# samd21g_minimal_board.net
KiCad netlist of a schematic drawn in EAGLE
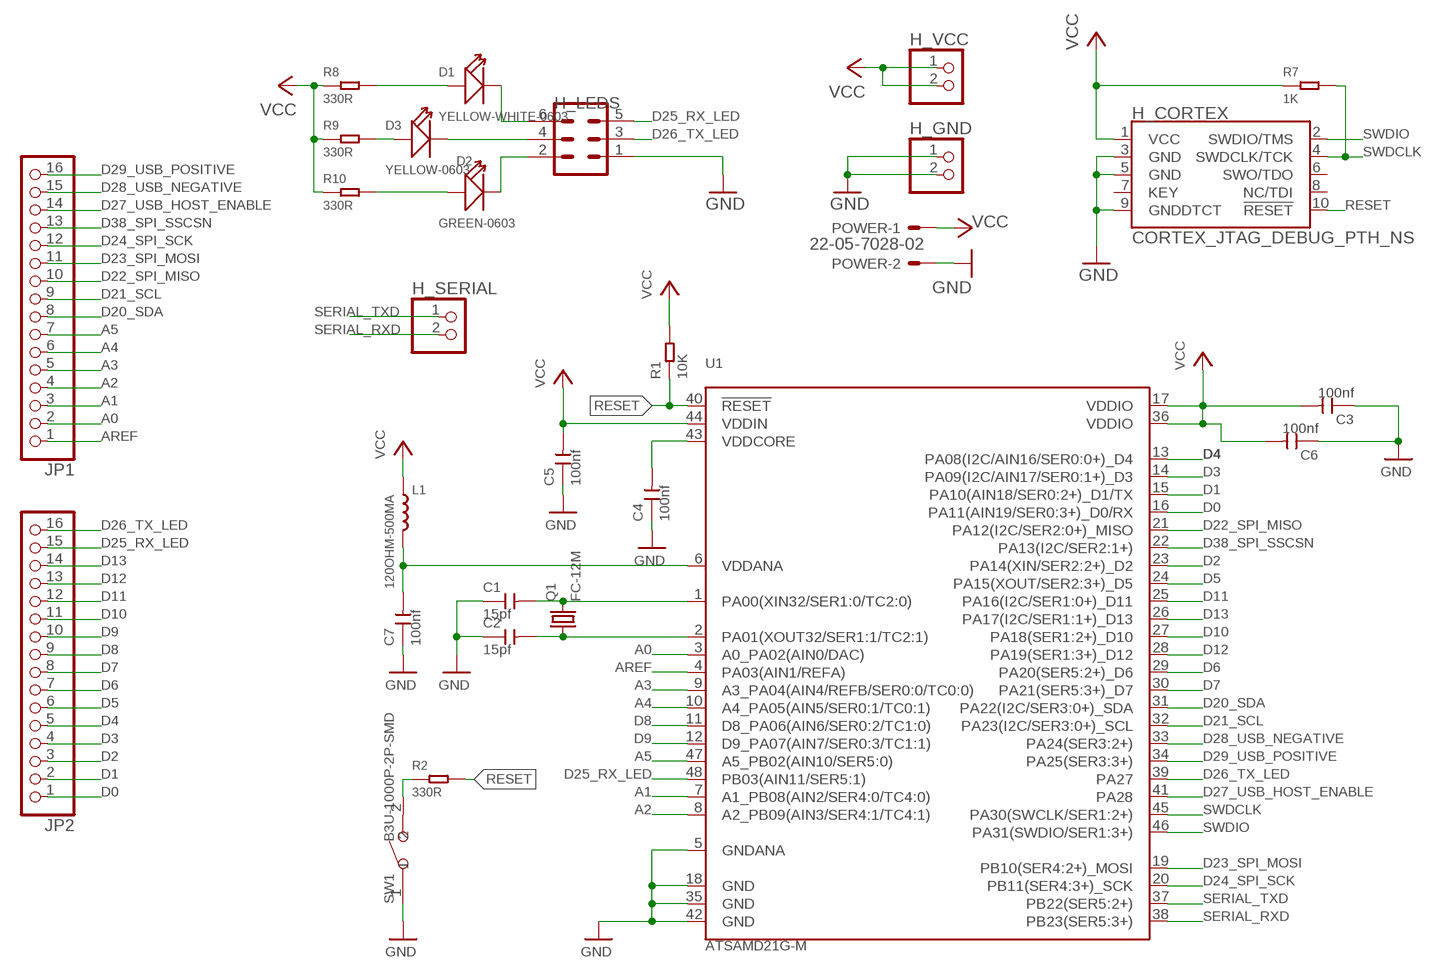
[diagram p0: schematic, sheet 1]

(export (version "E")
  (design (tool "Eeschema 10.0.6"))
  (components
    (comp (ref "C1")
      (value "15pf")
      (footprint "eagle-import:C0402")
      (fields (field (name "MPN") "GRM1555C1H150JA01D"))
      (libsource (lib "eagle-import") (part "CERAMIC-15PF-50V-5%-NPO(0402)"))
    )
    (comp (ref "C2")
      (value "15pf")
      (footprint "eagle-import:C0402")
      (fields (field (name "MPN") "GRM1555C1H150JA01D"))
      (libsource (lib "eagle-import") (part "CERAMIC-15PF-50V-5%-NPO(0402)"))
    )
    (comp (ref "C3")
      (value "100nf")
      (footprint "eagle-import:C0805")
      (fields (field (name "MPN") "CC0805KRX7R9BB104"))
      (libsource (lib "eagle-import") (part "CERAMIC-100NF-50V-10%-X7R(0805)"))
    )
    (comp (ref "C4")
      (value "100nf")
      (footprint "eagle-import:C0805")
      (fields (field (name "MPN") "CC0805KRX7R9BB104"))
      (libsource (lib "eagle-import") (part "CERAMIC-100NF-50V-10%-X7R(0805)"))
    )
    (comp (ref "C5")
      (value "100nf")
      (footprint "eagle-import:C0805")
      (fields (field (name "MPN") "CC0805KRX7R9BB104"))
      (libsource (lib "eagle-import") (part "CERAMIC-100NF-50V-10%-X7R(0805)"))
    )
    (comp (ref "C6")
      (value "100nf")
      (footprint "eagle-import:C0805")
      (fields (field (name "MPN") "CC0805KRX7R9BB104"))
      (libsource (lib "eagle-import") (part "CERAMIC-100NF-50V-10%-X7R(0805)"))
    )
    (comp (ref "C7")
      (value "100nf")
      (footprint "eagle-import:C0805")
      (fields (field (name "MPN") "CC0805KRX7R9BB104"))
      (libsource (lib "eagle-import") (part "CERAMIC-100NF-50V-10%-X7R(0805)"))
    )
    (comp (ref "D1")
      (value "YELLOW-WHITE-0603")
      (footprint "eagle-import:LED-0603")
      (fields (field (name "MPN") "ADL-0603W"))
      (libsource (lib "eagle-import") (part "SMD-LED-YELLOW-WHITE(0603)"))
    )
    (comp (ref "D2")
      (value "GREEN-0603")
      (footprint "eagle-import:LED-0603")
      (fields (field (name "MPN") "19-217-G7C-AN1P2-3T"))
      (libsource (lib "eagle-import") (part "SMD-LED-CLEAR-GREEN(0603)"))
    )
    (comp (ref "D3")
      (value "YELLOW-0603")
      (footprint "eagle-import:LED-0603")
      (fields (field (name "MPN") "19-217-Y5C-AM1N1VY-3T"))
      (libsource (lib "eagle-import") (part "SMD-LED-CLEAR-YELLOW(0603)"))
    )
    (comp (ref "H_CORTEX")
      (value "CORTEX_JTAG_DEBUG_PTH_NS")
      (footprint "eagle-import:2X5-PTH-1.27MM-NO_SILK")
      (libsource (lib "eagle-import") (part "CORTEX_JTAG_DEBUG_PTH_NS"))
    )
    (comp (ref "H_GND")
      (value "PINHD-1X2")
      (footprint "eagle-import:1X02")
      (libsource (lib "eagle-import") (part "PINHD-1X2"))
    )
    (comp (ref "H_LEDS")
      (value "M_2R03_50MIL-V2")
      (footprint "eagle-import:M_2R03_50MIL-V2")
      (libsource (lib "eagle-import") (part "M_2R03_50MIL-V2"))
    )
    (comp (ref "H_SERIAL")
      (value "PINHD-1X2")
      (footprint "eagle-import:1X02")
      (libsource (lib "eagle-import") (part "PINHD-1X2"))
    )
    (comp (ref "H_VCC")
      (value "PINHD-1X2")
      (footprint "eagle-import:1X02")
      (libsource (lib "eagle-import") (part "PINHD-1X2"))
    )
    (comp (ref "JP1")
      (value "PINHD-1X16")
      (footprint "eagle-import:1X16")
      (libsource (lib "eagle-import") (part "PINHD-1X16"))
    )
    (comp (ref "JP2")
      (value "PINHD-1X16")
      (footprint "eagle-import:1X16")
      (libsource (lib "eagle-import") (part "PINHD-1X16"))
    )
    (comp (ref "L1")
      (value "120OHM-500MA")
      (footprint "eagle-import:L0603")
      (fields (field (name "MPN") "BLM18AG121SN1D"))
      (libsource (lib "eagle-import") (part "SMD-FERRITE-CHIP-120-OHM-500MA(0603)"))
    )
    (comp (ref "POWER")
      (value "22-05-7028-02")
      (footprint "eagle-import:7395-02")
      (fields (field (name "MF") "MOLEX"))
      (libsource (lib "eagle-import") (part "22-?-0205-7028"))
    )
    (comp (ref "Q1")
      (value "FC-12M")
      (footprint "eagle-import:FC-12M")
      (libsource (lib "eagle-import") (part "FC-12M"))
    )
    (comp (ref "R1")
      (value "10K")
      (footprint "eagle-import:R0805")
      (fields (field (name "MPN") "RC0805FR-0710KL"))
      (libsource (lib "eagle-import") (part "SMD-RES-10K-1%-1/8W(0805)"))
    )
    (comp (ref "R2")
      (value "330R")
      (footprint "eagle-import:R0805")
      (fields (field (name "MPN") "RC0805JR-071KL") (field (name "MPN_1") "RC0805FR-07330RL"))
      (libsource (lib "eagle-import") (part "SMD-RES-330R-1%-1/8W(0805)"))
    )
    (comp (ref "R7")
      (value "1K")
      (footprint "eagle-import:R0805")
      (fields (field (name "MPN") "RC0805JR-071KL"))
      (libsource (lib "eagle-import") (part "SMD-RES-1K-5%-1/8W(0805)"))
    )
    (comp (ref "R8")
      (value "330R")
      (footprint "eagle-import:R0805")
      (fields (field (name "MPN") "RC0805JR-071KL") (field (name "MPN_1") "RC0805FR-07330RL"))
      (libsource (lib "eagle-import") (part "SMD-RES-330R-1%-1/8W(0805)"))
    )
    (comp (ref "R9")
      (value "330R")
      (footprint "eagle-import:R0805")
      (fields (field (name "MPN") "RC0805JR-071KL") (field (name "MPN_1") "RC0805FR-07330RL"))
      (libsource (lib "eagle-import") (part "SMD-RES-330R-1%-1/8W(0805)"))
    )
    (comp (ref "R10")
      (value "330R")
      (footprint "eagle-import:R0805")
      (fields (field (name "MPN") "RC0805JR-071KL") (field (name "MPN_1") "RC0805FR-07330RL"))
      (libsource (lib "eagle-import") (part "SMD-RES-330R-1%-1/8W(0805)"))
    )
    (comp (ref "SW1")
      (value "B3U-1000P-2P-SMD")
      (footprint "eagle-import:SW2-2.6-3.0X2.5X1.2+0.4MM")
      (fields (field (name "SPICEPREFIX") "B"))
      (libsource (lib "eagle-import") (part "SMD-BUTTON(2P-3.0X2.5X1.2+0.4MM)-B3U-1000P-2P-SMD"))
    )
    (comp (ref "U1")
      (value "ATSAMD21G-M")
      (footprint "eagle-import:QFN-48")
      (libsource (lib "eagle-import") (part "ATSAMD21G-M"))
    )
  )
  (nets
    (net (code "1") (name "/A0") (class "Default")
      (node (ref "JP1") (pin "2") (pinfunction "2_2") (pintype "passive"))
      (node (ref "U1") (pin "3") (pinfunction "A0_PA02(AIN0/DAC)_3") (pintype "bidirectional"))
    )
    (net (code "2") (name "/A1") (class "Default")
      (node (ref "JP1") (pin "3") (pinfunction "3_3") (pintype "passive"))
      (node (ref "U1") (pin "7") (pinfunction "A1_PB08(AIN2/SER4:0/TC4:0)_7") (pintype "bidirectional"))
    )
    (net (code "3") (name "/A2") (class "Default")
      (node (ref "JP1") (pin "4") (pinfunction "4_4") (pintype "passive"))
      (node (ref "U1") (pin "8") (pinfunction "A2_PB09(AIN3/SER4:1/TC4:1)_8") (pintype "bidirectional"))
    )
    (net (code "4") (name "/A3") (class "Default")
      (node (ref "JP1") (pin "5") (pinfunction "5_5") (pintype "passive"))
      (node (ref "U1") (pin "9") (pinfunction "A3_PA04(AIN4/REFB/SER0:0/TC0:0)_9") (pintype "bidirectional"))
    )
    (net (code "5") (name "/A4") (class "Default")
      (node (ref "JP1") (pin "6") (pinfunction "6_6") (pintype "passive"))
      (node (ref "U1") (pin "10") (pinfunction "A4_PA05(AIN5/SER0:1/TC0:1)_10") (pintype "bidirectional"))
    )
    (net (code "6") (name "/A5") (class "Default")
      (node (ref "JP1") (pin "7") (pinfunction "7_7") (pintype "passive"))
      (node (ref "U1") (pin "47") (pinfunction "A5_PB02(AIN10/SER5:0)_47") (pintype "bidirectional"))
    )
    (net (code "7") (name "/AREF") (class "Default")
      (node (ref "JP1") (pin "1") (pinfunction "1_1") (pintype "passive"))
      (node (ref "U1") (pin "4") (pinfunction "PA03(AIN1/REFA)_4") (pintype "bidirectional"))
    )
    (net (code "8") (name "/D0") (class "Default")
      (node (ref "JP2") (pin "1") (pinfunction "1_1") (pintype "passive"))
      (node (ref "U1") (pin "16") (pinfunction "PA11(AIN19/SER0:3+)_D0/RX_16") (pintype "bidirectional"))
    )
    (net (code "9") (name "/D1") (class "Default")
      (node (ref "JP2") (pin "2") (pinfunction "2_2") (pintype "passive"))
      (node (ref "U1") (pin "15") (pinfunction "PA10(AIN18/SER0:2+)_D1/TX_15") (pintype "bidirectional"))
    )
    (net (code "10") (name "/D2") (class "Default")
      (node (ref "JP2") (pin "3") (pinfunction "3_3") (pintype "passive"))
      (node (ref "U1") (pin "23") (pinfunction "PA14(XIN/SER2:2+)_D2_23") (pintype "bidirectional"))
    )
    (net (code "11") (name "/D3") (class "Default")
      (node (ref "JP2") (pin "4") (pinfunction "4_4") (pintype "passive"))
      (node (ref "U1") (pin "14") (pinfunction "PA09(I2C/AIN17/SER0:1+)_D3_14") (pintype "bidirectional"))
    )
    (net (code "12") (name "/D4") (class "Default")
      (node (ref "JP2") (pin "5") (pinfunction "5_5") (pintype "passive"))
      (node (ref "U1") (pin "13") (pinfunction "PA08(I2C/AIN16/SER0:0+)_D4_13") (pintype "bidirectional"))
    )
    (net (code "13") (name "/D5") (class "Default")
      (node (ref "JP2") (pin "6") (pinfunction "6_6") (pintype "passive"))
      (node (ref "U1") (pin "24") (pinfunction "PA15(XOUT/SER2:3+)_D5_24") (pintype "bidirectional"))
    )
    (net (code "14") (name "/D6") (class "Default")
      (node (ref "JP2") (pin "7") (pinfunction "7_7") (pintype "passive"))
      (node (ref "U1") (pin "29") (pinfunction "PA20(SER5:2+)_D6_29") (pintype "bidirectional"))
    )
    (net (code "15") (name "/D7") (class "Default")
      (node (ref "JP2") (pin "8") (pinfunction "8_8") (pintype "passive"))
      (node (ref "U1") (pin "30") (pinfunction "PA21(SER5:3+)_D7_30") (pintype "bidirectional"))
    )
    (net (code "16") (name "/D8") (class "Default")
      (node (ref "JP2") (pin "9") (pinfunction "9_9") (pintype "passive"))
      (node (ref "U1") (pin "11") (pinfunction "D8_PA06(AIN6/SER0:2/TC1:0)_11") (pintype "bidirectional"))
    )
    (net (code "17") (name "/D9") (class "Default")
      (node (ref "JP2") (pin "10") (pinfunction "10_10") (pintype "passive"))
      (node (ref "U1") (pin "12") (pinfunction "D9_PA07(AIN7/SER0:3/TC1:1)_12") (pintype "bidirectional"))
    )
    (net (code "18") (name "/D10") (class "Default")
      (node (ref "JP2") (pin "11") (pinfunction "11_11") (pintype "passive"))
      (node (ref "U1") (pin "27") (pinfunction "PA18(SER1:2+)_D10_27") (pintype "bidirectional"))
    )
    (net (code "19") (name "/D11") (class "Default")
      (node (ref "JP2") (pin "12") (pinfunction "12_12") (pintype "passive"))
      (node (ref "U1") (pin "25") (pinfunction "PA16(I2C/SER1:0+)_D11_25") (pintype "bidirectional"))
    )
    (net (code "20") (name "/D12") (class "Default")
      (node (ref "JP2") (pin "13") (pinfunction "13_13") (pintype "passive"))
      (node (ref "U1") (pin "28") (pinfunction "PA19(SER1:3+)_D12_28") (pintype "bidirectional"))
    )
    (net (code "21") (name "/D13") (class "Default")
      (node (ref "JP2") (pin "14") (pinfunction "14_14") (pintype "passive"))
      (node (ref "U1") (pin "26") (pinfunction "PA17(I2C/SER1:1+)_D13_26") (pintype "bidirectional"))
    )
    (net (code "22") (name "/D20_SDA") (class "Default")
      (node (ref "JP1") (pin "8") (pinfunction "8_8") (pintype "passive"))
      (node (ref "U1") (pin "31") (pinfunction "PA22(I2C/SER3:0+)_SDA_31") (pintype "bidirectional"))
    )
    (net (code "23") (name "/D21_SCL") (class "Default")
      (node (ref "JP1") (pin "9") (pinfunction "9_9") (pintype "passive"))
      (node (ref "U1") (pin "32") (pinfunction "PA23(I2C/SER3:0+)_SCL_32") (pintype "bidirectional"))
    )
    (net (code "24") (name "/D22_SPI_MISO") (class "Default")
      (node (ref "JP1") (pin "10") (pinfunction "10_10") (pintype "passive"))
      (node (ref "U1") (pin "21") (pinfunction "PA12(I2C/SER2:0+)_MISO_21") (pintype "bidirectional"))
    )
    (net (code "25") (name "/D23_SPI_MOSI") (class "Default")
      (node (ref "JP1") (pin "11") (pinfunction "11_11") (pintype "passive"))
      (node (ref "U1") (pin "19") (pinfunction "PB10(SER4:2+)_MOSI_19") (pintype "bidirectional"))
    )
    (net (code "26") (name "/D24_SPI_SCK") (class "Default")
      (node (ref "JP1") (pin "12") (pinfunction "12_12") (pintype "passive"))
      (node (ref "U1") (pin "20") (pinfunction "PB11(SER4:3+)_SCK_20") (pintype "bidirectional"))
    )
    (net (code "27") (name "/D25_RX_LED") (class "Default")
      (node (ref "H_LEDS") (pin "5") (pinfunction "5_5") (pintype "bidirectional"))
      (node (ref "JP2") (pin "15") (pinfunction "15_15") (pintype "passive"))
      (node (ref "U1") (pin "48") (pinfunction "PB03(AIN11/SER5:1)_48") (pintype "bidirectional"))
    )
    (net (code "28") (name "/D26_TX_LED") (class "Default")
      (node (ref "H_LEDS") (pin "3") (pinfunction "3_3") (pintype "bidirectional"))
      (node (ref "JP2") (pin "16") (pinfunction "16_16") (pintype "passive"))
      (node (ref "U1") (pin "39") (pinfunction "PA27_39") (pintype "bidirectional"))
    )
    (net (code "29") (name "/D27_USB_HOST_ENABLE") (class "Default")
      (node (ref "JP1") (pin "14") (pinfunction "14_14") (pintype "passive"))
      (node (ref "U1") (pin "41") (pinfunction "PA28_41") (pintype "bidirectional"))
    )
    (net (code "30") (name "/D28_USB_NEGATIVE") (class "Default")
      (node (ref "JP1") (pin "15") (pinfunction "15_15") (pintype "passive"))
      (node (ref "U1") (pin "33") (pinfunction "PA24(SER3:2+)_33") (pintype "bidirectional"))
    )
    (net (code "31") (name "/D29_USB_POSITIVE") (class "Default")
      (node (ref "JP1") (pin "16") (pinfunction "16_16") (pintype "passive"))
      (node (ref "U1") (pin "34") (pinfunction "PA25(SER3:3+)_34") (pintype "bidirectional"))
    )
    (net (code "32") (name "/D38_SPI_SSCSN") (class "Default")
      (node (ref "JP1") (pin "13") (pinfunction "13_13") (pintype "passive"))
      (node (ref "U1") (pin "22") (pinfunction "PA13(I2C/SER2:1+)_22") (pintype "bidirectional"))
    )
    (net (code "33") (name "/SERIAL_RXD") (class "Default")
      (node (ref "H_SERIAL") (pin "2") (pinfunction "2_2") (pintype "passive"))
      (node (ref "U1") (pin "38") (pinfunction "PB23(SER5:3+)_38") (pintype "bidirectional"))
    )
    (net (code "34") (name "/SERIAL_TXD") (class "Default")
      (node (ref "H_SERIAL") (pin "1") (pinfunction "1_1") (pintype "passive"))
      (node (ref "U1") (pin "37") (pinfunction "PB22(SER5:2+)_37") (pintype "bidirectional"))
    )
    (net (code "35") (name "/SWDCLK") (class "Default")
      (node (ref "H_CORTEX") (pin "4") (pinfunction "SWDCLK/TCK_4") (pintype "bidirectional"))
      (node (ref "R7") (pin "2") (pinfunction "2_2") (pintype "passive"))
      (node (ref "U1") (pin "45") (pinfunction "PA30(SWCLK/SER1:2+)_45") (pintype "bidirectional"))
    )
    (net (code "36") (name "/SWDIO") (class "Default")
      (node (ref "H_CORTEX") (pin "2") (pinfunction "SWDIO/TMS_2") (pintype "bidirectional"))
      (node (ref "U1") (pin "46") (pinfunction "PA31(SWDIO/SER1:3+)_46") (pintype "bidirectional"))
    )
    (net (code "37") (name "GND") (class "Default")
      (node (ref "C1") (pin "1") (pinfunction "1_1") (pintype "passive"))
      (node (ref "C2") (pin "1") (pinfunction "1_1") (pintype "passive"))
      (node (ref "C3") (pin "1") (pinfunction "1_1") (pintype "passive"))
      (node (ref "C4") (pin "1") (pinfunction "1_1") (pintype "passive"))
      (node (ref "C5") (pin "1") (pinfunction "1_1") (pintype "passive"))
      (node (ref "C6") (pin "1") (pinfunction "1_1") (pintype "passive"))
      (node (ref "C7") (pin "1") (pinfunction "1_1") (pintype "passive"))
      (node (ref "H_CORTEX") (pin "3") (pinfunction "GND_3") (pintype "bidirectional"))
      (node (ref "H_CORTEX") (pin "5") (pinfunction "GND_5") (pintype "bidirectional"))
      (node (ref "H_CORTEX") (pin "9") (pinfunction "GNDDTCT_9") (pintype "bidirectional"))
      (node (ref "H_GND") (pin "1") (pinfunction "1_1") (pintype "passive"))
      (node (ref "H_GND") (pin "2") (pinfunction "2_2") (pintype "passive"))
      (node (ref "H_LEDS") (pin "1") (pinfunction "1_1") (pintype "bidirectional"))
      (node (ref "POWER") (pin "2") (pinfunction "S_2") (pintype "passive"))
      (node (ref "SW1") (pin "1") (pinfunction "1_1") (pintype "bidirectional"))
      (node (ref "U1") (pin "18") (pinfunction "GND_18") (pintype "bidirectional"))
      (node (ref "U1") (pin "35") (pinfunction "GND_35") (pintype "bidirectional"))
      (node (ref "U1") (pin "42") (pinfunction "GND_42") (pintype "bidirectional"))
      (node (ref "U1") (pin "5") (pinfunction "GNDANA_5") (pintype "bidirectional"))
    )
    (net (code "38") (name "Net-(D1-Pad+)") (class "Default")
      (node (ref "D1") (pin "+") (pinfunction "+_+") (pintype "passive"))
      (node (ref "R8") (pin "2") (pinfunction "2_2") (pintype "passive"))
    )
    (net (code "39") (name "Net-(D1-Pad-)") (class "Default")
      (node (ref "D1") (pin "-") (pinfunction "-_-") (pintype "passive"))
      (node (ref "H_LEDS") (pin "6") (pinfunction "6_6") (pintype "bidirectional"))
    )
    (net (code "40") (name "Net-(D2-Pad+)") (class "Default")
      (node (ref "D2") (pin "+") (pinfunction "+_+") (pintype "passive"))
      (node (ref "R10") (pin "2") (pinfunction "2_2") (pintype "passive"))
    )
    (net (code "41") (name "Net-(D2-Pad-)") (class "Default")
      (node (ref "D2") (pin "-") (pinfunction "-_-") (pintype "passive"))
      (node (ref "H_LEDS") (pin "2") (pinfunction "2_2") (pintype "bidirectional"))
    )
    (net (code "42") (name "Net-(D3-Pad+)") (class "Default")
      (node (ref "D3") (pin "+") (pinfunction "+_+") (pintype "passive"))
      (node (ref "R9") (pin "2") (pinfunction "2_2") (pintype "passive"))
    )
    (net (code "43") (name "Net-(D3-Pad-)") (class "Default")
      (node (ref "D3") (pin "-") (pinfunction "-_-") (pintype "passive"))
      (node (ref "H_LEDS") (pin "4") (pinfunction "4_4") (pintype "bidirectional"))
    )
    (net (code "44") (name "Net-(R2-Pad1)") (class "Default")
      (node (ref "R2") (pin "1") (pinfunction "1_1") (pintype "passive"))
      (node (ref "SW1") (pin "2") (pinfunction "2_2") (pintype "bidirectional"))
    )
    (net (code "45") (name "Net-(U1-PA00(XIN32{slash}SER1:0{slash}TC2:0))") (class "Default")
      (node (ref "C1") (pin "2") (pinfunction "2_2") (pintype "passive"))
      (node (ref "Q1") (pin "2") (pinfunction "2_2") (pintype "passive"))
      (node (ref "U1") (pin "1") (pinfunction "PA00(XIN32/SER1:0/TC2:0)_1") (pintype "bidirectional"))
    )
    (net (code "46") (name "Net-(U1-PA01(XOUT32{slash}SER1:1{slash}TC2:1))") (class "Default")
      (node (ref "C2") (pin "2") (pinfunction "2_2") (pintype "passive"))
      (node (ref "Q1") (pin "1") (pinfunction "1_1") (pintype "passive"))
      (node (ref "U1") (pin "2") (pinfunction "PA01(XOUT32/SER1:1/TC2:1)_2") (pintype "bidirectional"))
    )
    (net (code "47") (name "Net-(U1-VDDANA)") (class "Default")
      (node (ref "C7") (pin "2") (pinfunction "2_2") (pintype "passive"))
      (node (ref "L1") (pin "2") (pinfunction "2_2") (pintype "passive"))
      (node (ref "U1") (pin "6") (pinfunction "VDDANA_6") (pintype "bidirectional"))
    )
    (net (code "48") (name "Net-(U1-VDDCORE)") (class "Default")
      (node (ref "C4") (pin "2") (pinfunction "2_2") (pintype "passive"))
      (node (ref "U1") (pin "43") (pinfunction "VDDCORE_43") (pintype "bidirectional"))
    )
    (net (code "49") (name "RESET") (class "Default")
      (node (ref "H_CORTEX") (pin "10") (pinfunction "~{RESET}_10") (pintype "bidirectional"))
      (node (ref "R1") (pin "1") (pinfunction "1_1") (pintype "passive"))
      (node (ref "R2") (pin "2") (pinfunction "2_2") (pintype "passive"))
      (node (ref "U1") (pin "40") (pinfunction "~{RESET}_40") (pintype "bidirectional"))
    )
    (net (code "50") (name "VCC") (class "Default")
      (node (ref "C3") (pin "2") (pinfunction "2_2") (pintype "passive"))
      (node (ref "C5") (pin "2") (pinfunction "2_2") (pintype "passive"))
      (node (ref "C6") (pin "2") (pinfunction "2_2") (pintype "passive"))
      (node (ref "H_CORTEX") (pin "1") (pinfunction "VCC_1") (pintype "bidirectional"))
      (node (ref "H_VCC") (pin "1") (pinfunction "1_1") (pintype "passive"))
      (node (ref "H_VCC") (pin "2") (pinfunction "2_2") (pintype "passive"))
      (node (ref "L1") (pin "1") (pinfunction "1_1") (pintype "passive"))
      (node (ref "POWER") (pin "1") (pinfunction "S_1") (pintype "passive"))
      (node (ref "R1") (pin "2") (pinfunction "2_2") (pintype "passive"))
      (node (ref "R10") (pin "1") (pinfunction "1_1") (pintype "passive"))
      (node (ref "R7") (pin "1") (pinfunction "1_1") (pintype "passive"))
      (node (ref "R8") (pin "1") (pinfunction "1_1") (pintype "passive"))
      (node (ref "R9") (pin "1") (pinfunction "1_1") (pintype "passive"))
      (node (ref "U1") (pin "17") (pinfunction "VDDIO_17") (pintype "bidirectional"))
      (node (ref "U1") (pin "36") (pinfunction "VDDIO_36") (pintype "bidirectional"))
      (node (ref "U1") (pin "44") (pinfunction "VDDIN_44") (pintype "bidirectional"))
    )
    (net (code "51") (name "unconnected-(H_CORTEX-KEY-Pad7)") (class "Default")
      (node (ref "H_CORTEX") (pin "7") (pinfunction "KEY_7") (pintype "bidirectional"))
    )
    (net (code "52") (name "unconnected-(H_CORTEX-NC{slash}TDI-Pad8)") (class "Default")
      (node (ref "H_CORTEX") (pin "8") (pinfunction "NC/TDI_8") (pintype "bidirectional"))
    )
    (net (code "53") (name "unconnected-(H_CORTEX-SWO{slash}TDO-Pad6)") (class "Default")
      (node (ref "H_CORTEX") (pin "6") (pinfunction "SWO/TDO_6") (pintype "bidirectional"))
    )
  )
)
